# Sch3.net
KiCad netlist of a schematic drawn in Altium Designer
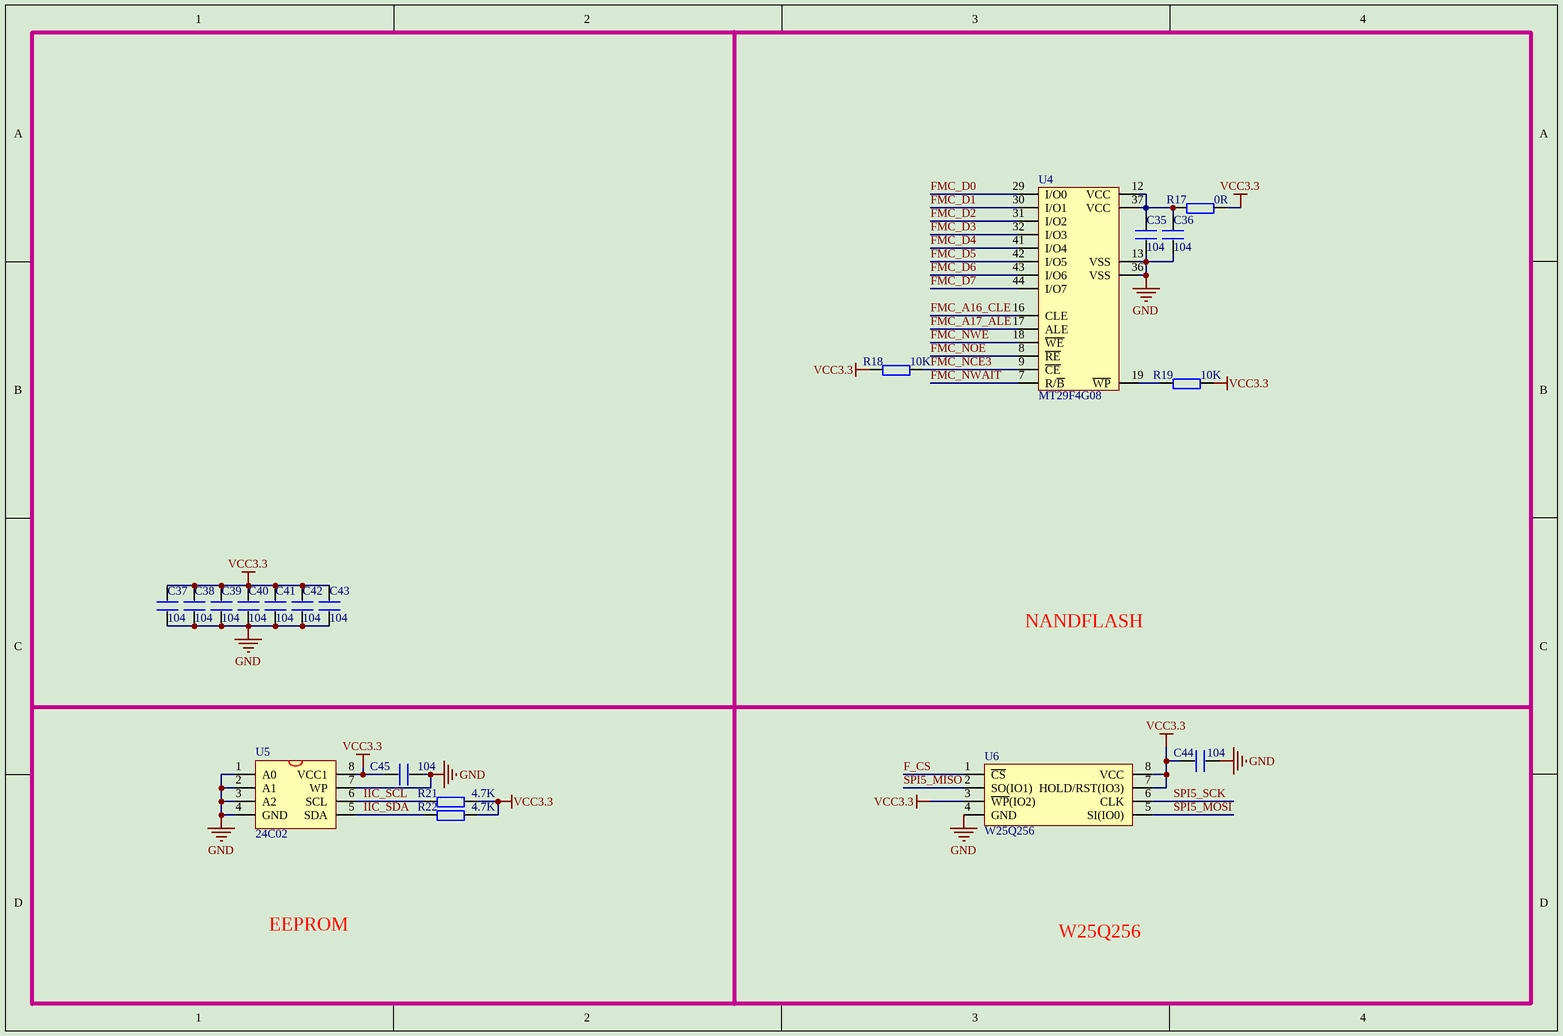
[diagram p0: Sch3.SchDoc]

(export (version "E")
  (design (tool "Eeschema 10.0.6"))
  (components
    (comp (ref "C35") (value "104") (footprint "0402") (libsource (lib "STM32F429_CORE") (part "C")))
    (comp (ref "C36") (value "104") (footprint "0402") (libsource (lib "STM32F429_CORE") (part "C")))
    (comp (ref "C37") (value "104") (footprint "0402") (libsource (lib "STM32F429_CORE") (part "C")))
    (comp (ref "C38") (value "104") (footprint "0402") (libsource (lib "STM32F429_CORE") (part "C")))
    (comp (ref "C39") (value "104") (footprint "0402") (libsource (lib "STM32F429_CORE") (part "C")))
    (comp (ref "C40") (value "104") (footprint "0402") (libsource (lib "STM32F429_CORE") (part "C")))
    (comp (ref "C41") (value "104") (footprint "0402") (libsource (lib "STM32F429_CORE") (part "C")))
    (comp (ref "C42") (value "104") (footprint "0402") (libsource (lib "STM32F429_CORE") (part "C")))
    (comp (ref "C43") (value "104") (footprint "0402") (libsource (lib "STM32F429_CORE") (part "C")))
    (comp (ref "C44") (value "104") (footprint "0402") (libsource (lib "STM32F429_CORE") (part "C")))
    (comp (ref "C45") (value "104") (footprint "0402") (libsource (lib "STM32F429_CORE") (part "C")))
    (comp (ref "R17") (value "0R") (footprint "0402") (libsource (lib "STM32F429_CORE") (part "R")))
    (comp (ref "R18") (value "10K") (footprint "0402") (libsource (lib "STM32F429_CORE") (part "R")))
    (comp (ref "R19") (value "10K") (footprint "0402") (libsource (lib "STM32F429_CORE") (part "R")))
    (comp (ref "R21") (value "4.7K") (footprint "0402") (libsource (lib "STM32F429_CORE") (part "R")))
    (comp (ref "R22") (value "4.7K") (footprint "0402") (libsource (lib "STM32F429_CORE") (part "R")))
    (comp (ref "U4")
      (value "MT29F4G08")
      (footprint "TSOP48")
      (description "256MB NAND FLASH")
      (libsource (lib "STM32F429_CORE") (part "K9F2G08U0C"))
    )
    (comp (ref "U5")
      (value "24C02")
      (footprint "SOP-8")
      (description "EEPROM")
      (libsource (lib "STM32F429_CORE") (part "24C256"))
    )
    (comp (ref "U6")
      (value "W25Q256")
      (footprint "WSON8")
      (description "W25Q128")
      (libsource (lib "STM32F429_CORE") (part "W25Q128"))
    )
  )
  (nets
    (net (code "1") (name "/FMC_A16_CLE") (class "Default")
      (node (ref "U4") (pin "16") (pinfunction "CLE_16") (pintype "passive"))
    )
    (net (code "2") (name "/FMC_A17_ALE") (class "Default")
      (node (ref "U4") (pin "17") (pinfunction "ALE_17") (pintype "passive"))
    )
    (net (code "3") (name "/FMC_D0") (class "Default")
      (node (ref "U4") (pin "29") (pinfunction "I/O0_29") (pintype "passive"))
    )
    (net (code "4") (name "/FMC_D1") (class "Default")
      (node (ref "U4") (pin "30") (pinfunction "I/O1_30") (pintype "passive"))
    )
    (net (code "5") (name "/FMC_D2") (class "Default")
      (node (ref "U4") (pin "31") (pinfunction "I/O2_31") (pintype "passive"))
    )
    (net (code "6") (name "/FMC_D3") (class "Default")
      (node (ref "U4") (pin "32") (pinfunction "I/O3_32") (pintype "passive"))
    )
    (net (code "7") (name "/FMC_D4") (class "Default")
      (node (ref "U4") (pin "41") (pinfunction "I/O4_41") (pintype "passive"))
    )
    (net (code "8") (name "/FMC_D5") (class "Default")
      (node (ref "U4") (pin "42") (pinfunction "I/O5_42") (pintype "passive"))
    )
    (net (code "9") (name "/FMC_D6") (class "Default")
      (node (ref "U4") (pin "43") (pinfunction "I/O6_43") (pintype "passive"))
    )
    (net (code "10") (name "/FMC_D7") (class "Default")
      (node (ref "U4") (pin "44") (pinfunction "I/O7_44") (pintype "passive"))
    )
    (net (code "11") (name "/FMC_NCE3") (class "Default")
      (node (ref "R18") (pin "2") (pintype "passive"))
      (node (ref "U4") (pin "9") (pinfunction "~{CE}_9") (pintype "passive"))
    )
    (net (code "12") (name "/FMC_NOE") (class "Default")
      (node (ref "U4") (pin "8") (pinfunction "~{RE}_8") (pintype "passive"))
    )
    (net (code "13") (name "/FMC_NWAIT") (class "Default")
      (node (ref "U4") (pin "7") (pinfunction "R/~{B}_7") (pintype "passive"))
    )
    (net (code "14") (name "/FMC_NWE") (class "Default")
      (node (ref "U4") (pin "18") (pinfunction "~{WE}_18") (pintype "passive"))
    )
    (net (code "15") (name "/F_CS") (class "Default")
      (node (ref "U6") (pin "1") (pinfunction "~{CS}_1") (pintype "passive"))
    )
    (net (code "16") (name "/IIC_SCL") (class "Default")
      (node (ref "R21") (pin "1") (pintype "passive"))
      (node (ref "U5") (pin "6") (pinfunction "SCL_6") (pintype "passive"))
    )
    (net (code "17") (name "/IIC_SDA") (class "Default")
      (node (ref "R22") (pin "1") (pintype "passive"))
      (node (ref "U5") (pin "5") (pinfunction "SDA_5") (pintype "passive"))
    )
    (net (code "18") (name "/SPI5_MISO") (class "Default")
      (node (ref "U6") (pin "2") (pinfunction "SO(IO1)_2") (pintype "passive"))
    )
    (net (code "19") (name "/SPI5_MOSI") (class "Default")
      (node (ref "U6") (pin "5") (pinfunction "SI(IO0)_5") (pintype "power_in"))
    )
    (net (code "20") (name "/SPI5_SCK") (class "Default")
      (node (ref "U6") (pin "6") (pinfunction "CLK_6") (pintype "passive"))
    )
    (net (code "21") (name "GND") (class "Default")
      (node (ref "C35") (pin "1") (pintype "passive"))
      (node (ref "C36") (pin "1") (pintype "passive"))
      (node (ref "C37") (pin "1") (pintype "passive"))
      (node (ref "C38") (pin "1") (pintype "passive"))
      (node (ref "C39") (pin "1") (pintype "passive"))
      (node (ref "C40") (pin "1") (pintype "passive"))
      (node (ref "C41") (pin "1") (pintype "passive"))
      (node (ref "C42") (pin "1") (pintype "passive"))
      (node (ref "C43") (pin "1") (pintype "passive"))
      (node (ref "C44") (pin "2") (pintype "passive"))
      (node (ref "C45") (pin "2") (pintype "passive"))
      (node (ref "U4") (pin "13") (pinfunction "VSS_13") (pintype "passive"))
      (node (ref "U4") (pin "36") (pinfunction "VSS_36") (pintype "passive"))
      (node (ref "U5") (pin "1") (pinfunction "A0_1") (pintype "passive"))
      (node (ref "U5") (pin "2") (pinfunction "A1_2") (pintype "passive"))
      (node (ref "U5") (pin "3") (pinfunction "A2_3") (pintype "passive"))
      (node (ref "U5") (pin "4") (pinfunction "GND_4") (pintype "passive"))
      (node (ref "U5") (pin "7") (pinfunction "WP_7") (pintype "passive"))
      (node (ref "U6") (pin "4") (pinfunction "GND_4") (pintype "passive"))
    )
    (net (code "22") (name "Net-(C35-Pad2)") (class "Default")
      (node (ref "C35") (pin "2") (pintype "passive"))
      (node (ref "C36") (pin "2") (pintype "passive"))
      (node (ref "R17") (pin "1") (pintype "passive"))
      (node (ref "U4") (pin "12") (pinfunction "VCC_12") (pintype "passive"))
      (node (ref "U4") (pin "37") (pinfunction "VCC_37") (pintype "passive"))
    )
    (net (code "23") (name "Net-(U4-~{WP})") (class "Default")
      (node (ref "R19") (pin "1") (pintype "passive"))
      (node (ref "U4") (pin "19") (pinfunction "~{WP}_19") (pintype "passive"))
    )
    (net (code "24") (name "VCC3.3") (class "Default")
      (node (ref "C37") (pin "2") (pintype "passive"))
      (node (ref "C38") (pin "2") (pintype "passive"))
      (node (ref "C39") (pin "2") (pintype "passive"))
      (node (ref "C40") (pin "2") (pintype "passive"))
      (node (ref "C41") (pin "2") (pintype "passive"))
      (node (ref "C42") (pin "2") (pintype "passive"))
      (node (ref "C43") (pin "2") (pintype "passive"))
      (node (ref "C44") (pin "1") (pintype "passive"))
      (node (ref "C45") (pin "1") (pintype "passive"))
      (node (ref "R17") (pin "2") (pintype "passive"))
      (node (ref "R18") (pin "1") (pintype "passive"))
      (node (ref "R19") (pin "2") (pintype "passive"))
      (node (ref "R21") (pin "2") (pintype "passive"))
      (node (ref "R22") (pin "2") (pintype "passive"))
      (node (ref "U5") (pin "8") (pinfunction "VCC1_8") (pintype "passive"))
      (node (ref "U6") (pin "3") (pinfunction "~{WP}(IO2)_3") (pintype "passive"))
      (node (ref "U6") (pin "7") (pinfunction "HOLD/RST(IO3)_7") (pintype "power_in"))
      (node (ref "U6") (pin "8") (pinfunction "VCC_8") (pintype "passive"))
    )
  )
)
